# WaterLevelIndicator.net
KiCad netlist of a schematic drawn in EAGLE
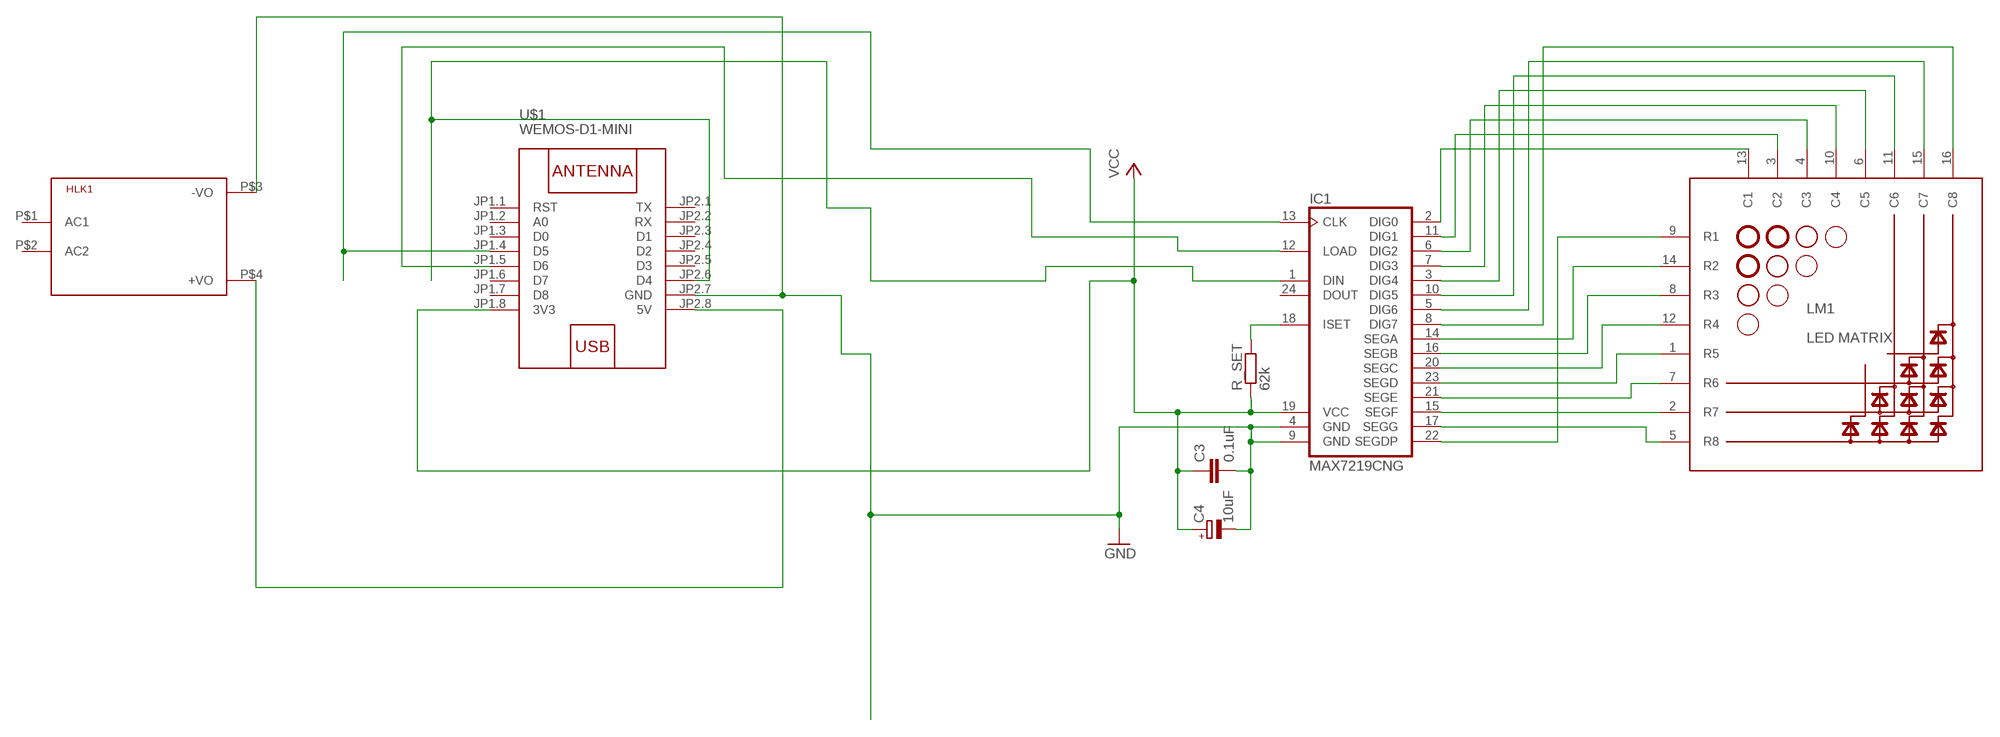
[diagram p0: schematic, sheet 1]

(export (version "E")
  (design (tool "Eeschema 10.0.6"))
  (components
    (comp (ref "C3")
      (value "0.1uF")
      (footprint "eagle-import:C025-024X044")
      (libsource (lib "eagle-import") (part "C-EU025-024X044"))
    )
    (comp (ref "C4")
      (value "10uF")
      (footprint "eagle-import:E2-5")
      (libsource (lib "eagle-import") (part "CPOL-EUE2-5"))
    )
    (comp (ref "HLK1")
      (value "HLK-PM013W")
      (footprint "eagle-import:HLK-PM01")
      (libsource (lib "eagle-import") (part "HLK-PM013W"))
    )
    (comp (ref "IC1")
      (value "MAX7219CNG")
      (footprint "eagle-import:DIL24-3")
      (fields (field (name "MF") "MAXIM"))
      (libsource (lib "eagle-import") (part "MAX7219CNG"))
    )
    (comp (ref "LM1")
      (value "LED MATRIX")
      (footprint "eagle-import:LED_MATRIX")
      (libsource (lib "eagle-import") (part "LD-1088BS_LED_MATRIX"))
    )
    (comp (ref "R_SET")
      (value "62k")
      (footprint "eagle-import:0207_10")
      (libsource (lib "eagle-import") (part "R-EU_0207/10"))
    )
    (comp (ref "U$1")
      (value "WEMOS-D1-MINI")
      (footprint "eagle-import:WEMOS-D1-MINI")
      (libsource (lib "eagle-import") (part "WEMOS-D1-MINI"))
    )
  )
  (nets
    (net (code "1") (name "GND") (class "Default")
      (node (ref "C3") (pin "2") (pinfunction "2_2") (pintype "passive"))
      (node (ref "C4") (pin "-") (pinfunction "-_-") (pintype "passive"))
      (node (ref "HLK1") (pin "P$3") (pinfunction "-VO_P$3") (pintype "bidirectional"))
      (node (ref "IC1") (pin "4") (pinfunction "GND_4") (pintype "power_in"))
      (node (ref "IC1") (pin "9") (pinfunction "GND_9") (pintype "power_in"))
      (node (ref "U$1") (pin "JP2.7") (pinfunction "GND_JP2.7") (pintype "power_in"))
    )
    (net (code "2") (name "Net-(HLK1-+VO)") (class "Default")
      (node (ref "HLK1") (pin "P$4") (pinfunction "+VO_P$4") (pintype "bidirectional"))
      (node (ref "U$1") (pin "JP2.8") (pinfunction "5V_JP2.8") (pintype "power_in"))
    )
    (net (code "3") (name "Net-(IC1-CLK)") (class "Default")
      (node (ref "IC1") (pin "13") (pinfunction "CLK_13") (pintype "input"))
      (node (ref "U$1") (pin "JP1.4") (pinfunction "D5_JP1.4") (pintype "bidirectional"))
    )
    (net (code "4") (name "Net-(IC1-DIG0)") (class "Default")
      (node (ref "IC1") (pin "2") (pinfunction "DIG0_2") (pintype "output"))
      (node (ref "LM1") (pin "13") (pinfunction "C1_13") (pintype "input"))
    )
    (net (code "5") (name "Net-(IC1-DIG1)") (class "Default")
      (node (ref "IC1") (pin "11") (pinfunction "DIG1_11") (pintype "output"))
      (node (ref "LM1") (pin "3") (pinfunction "C2_3") (pintype "input"))
    )
    (net (code "6") (name "Net-(IC1-DIG2)") (class "Default")
      (node (ref "IC1") (pin "6") (pinfunction "DIG2_6") (pintype "output"))
      (node (ref "LM1") (pin "4") (pinfunction "C3_4") (pintype "input"))
    )
    (net (code "7") (name "Net-(IC1-DIG3)") (class "Default")
      (node (ref "IC1") (pin "7") (pinfunction "DIG3_7") (pintype "output"))
      (node (ref "LM1") (pin "10") (pinfunction "C4_10") (pintype "input"))
    )
    (net (code "8") (name "Net-(IC1-DIG4)") (class "Default")
      (node (ref "IC1") (pin "3") (pinfunction "DIG4_3") (pintype "output"))
      (node (ref "LM1") (pin "6") (pinfunction "C5_6") (pintype "input"))
    )
    (net (code "9") (name "Net-(IC1-DIG5)") (class "Default")
      (node (ref "IC1") (pin "10") (pinfunction "DIG5_10") (pintype "output"))
      (node (ref "LM1") (pin "11") (pinfunction "C6_11") (pintype "input"))
    )
    (net (code "10") (name "Net-(IC1-DIG6)") (class "Default")
      (node (ref "IC1") (pin "5") (pinfunction "DIG6_5") (pintype "output"))
      (node (ref "LM1") (pin "15") (pinfunction "C7_15") (pintype "input"))
    )
    (net (code "11") (name "Net-(IC1-DIG7)") (class "Default")
      (node (ref "IC1") (pin "8") (pinfunction "DIG7_8") (pintype "output"))
      (node (ref "LM1") (pin "16") (pinfunction "C8_16") (pintype "input"))
    )
    (net (code "12") (name "Net-(IC1-DIN)") (class "Default")
      (node (ref "IC1") (pin "1") (pinfunction "DIN_1") (pintype "input"))
      (node (ref "U$1") (pin "JP2.6") (pinfunction "D4_JP2.6") (pintype "bidirectional"))
    )
    (net (code "13") (name "Net-(IC1-ISET)") (class "Default")
      (node (ref "IC1") (pin "18") (pinfunction "ISET_18") (pintype "input"))
      (node (ref "R_SET") (pin "2") (pinfunction "2_2") (pintype "passive"))
    )
    (net (code "14") (name "Net-(IC1-LOAD)") (class "Default")
      (node (ref "IC1") (pin "12") (pinfunction "LOAD_12") (pintype "input"))
      (node (ref "U$1") (pin "JP1.5") (pinfunction "D6_JP1.5") (pintype "bidirectional"))
    )
    (net (code "15") (name "Net-(IC1-SEGA)") (class "Default")
      (node (ref "IC1") (pin "14") (pinfunction "SEGA_14") (pintype "output"))
      (node (ref "LM1") (pin "14") (pinfunction "R2_14") (pintype "input"))
    )
    (net (code "16") (name "Net-(IC1-SEGB)") (class "Default")
      (node (ref "IC1") (pin "16") (pinfunction "SEGB_16") (pintype "output"))
      (node (ref "LM1") (pin "8") (pinfunction "R3_8") (pintype "input"))
    )
    (net (code "17") (name "Net-(IC1-SEGC)") (class "Default")
      (node (ref "IC1") (pin "20") (pinfunction "SEGC_20") (pintype "output"))
      (node (ref "LM1") (pin "12") (pinfunction "R4_12") (pintype "input"))
    )
    (net (code "18") (name "Net-(IC1-SEGD)") (class "Default")
      (node (ref "IC1") (pin "23") (pinfunction "SEGD_23") (pintype "output"))
      (node (ref "LM1") (pin "1") (pinfunction "R5_1") (pintype "input"))
    )
    (net (code "19") (name "Net-(IC1-SEGDP)") (class "Default")
      (node (ref "IC1") (pin "22") (pinfunction "SEGDP_22") (pintype "output"))
      (node (ref "LM1") (pin "9") (pinfunction "R1_9") (pintype "input"))
    )
    (net (code "20") (name "Net-(IC1-SEGE)") (class "Default")
      (node (ref "IC1") (pin "21") (pinfunction "SEGE_21") (pintype "output"))
      (node (ref "LM1") (pin "7") (pinfunction "R6_7") (pintype "input"))
    )
    (net (code "21") (name "Net-(IC1-SEGF)") (class "Default")
      (node (ref "IC1") (pin "15") (pinfunction "SEGF_15") (pintype "output"))
      (node (ref "LM1") (pin "2") (pinfunction "R7_2") (pintype "input"))
    )
    (net (code "22") (name "Net-(IC1-SEGG)") (class "Default")
      (node (ref "IC1") (pin "17") (pinfunction "SEGG_17") (pintype "output"))
      (node (ref "LM1") (pin "5") (pinfunction "R8_5") (pintype "input"))
    )
    (net (code "23") (name "VCC") (class "Default")
      (node (ref "C3") (pin "1") (pinfunction "1_1") (pintype "passive"))
      (node (ref "C4") (pin "+") (pinfunction "+_+") (pintype "passive"))
      (node (ref "IC1") (pin "19") (pinfunction "VCC_19") (pintype "power_in"))
      (node (ref "R_SET") (pin "1") (pinfunction "1_1") (pintype "passive"))
      (node (ref "U$1") (pin "JP1.8") (pinfunction "3V3_JP1.8") (pintype "power_in"))
    )
    (net (code "24") (name "unconnected-(HLK1-AC1-PadP$1)") (class "Default")
      (node (ref "HLK1") (pin "P$1") (pinfunction "AC1_P$1") (pintype "bidirectional"))
    )
    (net (code "25") (name "unconnected-(HLK1-AC2-PadP$2)") (class "Default")
      (node (ref "HLK1") (pin "P$2") (pinfunction "AC2_P$2") (pintype "bidirectional"))
    )
    (net (code "26") (name "unconnected-(IC1-DOUT-Pad24)") (class "Default")
      (node (ref "IC1") (pin "24") (pinfunction "DOUT_24") (pintype "output"))
    )
    (net (code "27") (name "unconnected-(U$1-A0-PadJP1.2)") (class "Default")
      (node (ref "U$1") (pin "JP1.2") (pinfunction "A0_JP1.2") (pintype "bidirectional"))
    )
    (net (code "28") (name "unconnected-(U$1-D0-PadJP1.3)") (class "Default")
      (node (ref "U$1") (pin "JP1.3") (pinfunction "D0_JP1.3") (pintype "bidirectional"))
    )
    (net (code "29") (name "unconnected-(U$1-D1-PadJP2.3)") (class "Default")
      (node (ref "U$1") (pin "JP2.3") (pinfunction "D1_JP2.3") (pintype "bidirectional"))
    )
    (net (code "30") (name "unconnected-(U$1-D2-PadJP2.4)") (class "Default")
      (node (ref "U$1") (pin "JP2.4") (pinfunction "D2_JP2.4") (pintype "bidirectional"))
    )
    (net (code "31") (name "unconnected-(U$1-D3-PadJP2.5)") (class "Default")
      (node (ref "U$1") (pin "JP2.5") (pinfunction "D3_JP2.5") (pintype "bidirectional"))
    )
    (net (code "32") (name "unconnected-(U$1-D7-PadJP1.6)") (class "Default")
      (node (ref "U$1") (pin "JP1.6") (pinfunction "D7_JP1.6") (pintype "bidirectional"))
    )
    (net (code "33") (name "unconnected-(U$1-D8-PadJP1.7)") (class "Default")
      (node (ref "U$1") (pin "JP1.7") (pinfunction "D8_JP1.7") (pintype "bidirectional"))
    )
    (net (code "34") (name "unconnected-(U$1-RST-PadJP1.1)") (class "Default")
      (node (ref "U$1") (pin "JP1.1") (pinfunction "RST_JP1.1") (pintype "bidirectional"))
    )
    (net (code "35") (name "unconnected-(U$1-RX-PadJP2.2)") (class "Default")
      (node (ref "U$1") (pin "JP2.2") (pinfunction "RX_JP2.2") (pintype "bidirectional"))
    )
    (net (code "36") (name "unconnected-(U$1-TX-PadJP2.1)") (class "Default")
      (node (ref "U$1") (pin "JP2.1") (pinfunction "TX_JP2.1") (pintype "bidirectional"))
    )
  )
)
